# main.net
KiCad netlist of a schematic drawn in Altium Designer
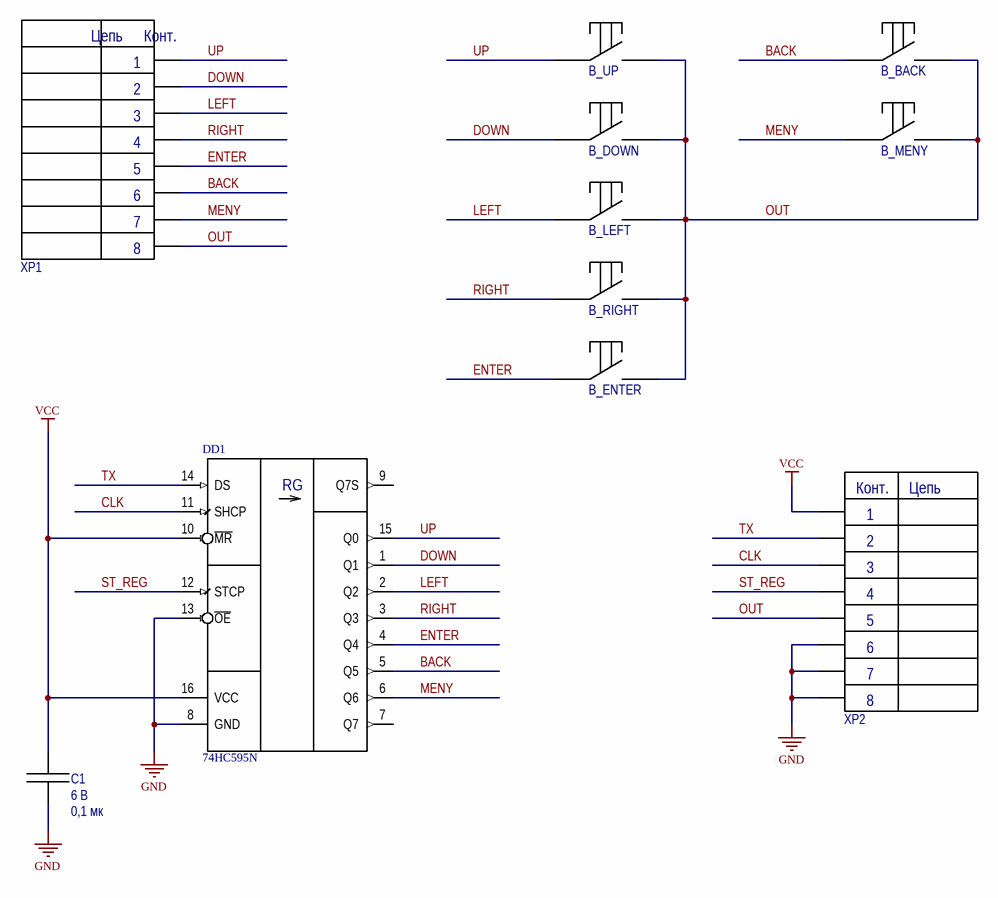
[diagram p0: main.SchDoc]

(export (version "E")
  (design (tool "Eeschema 10.0.6"))
  (components
    (comp (ref "B_BACK")
      (value "Tact_switch")
      (footprint "Tact_switch_6x6x5")
      (description "SMD pushbutton")
      (fields (field (name "MANUFACTURER") "NONAME"))
      (libsource (lib "connectors+switches") (part "Tact_switch"))
    )
    (comp (ref "B_DOWN")
      (value "Tact_switch")
      (footprint "Tact_switch_6x6x5")
      (description "SMD pushbutton")
      (fields (field (name "MANUFACTURER") "NONAME"))
      (libsource (lib "connectors+switches") (part "Tact_switch"))
    )
    (comp (ref "B_ENTER")
      (value "Tact_switch")
      (footprint "Tact_switch_6x6x5")
      (description "SMD pushbutton")
      (fields (field (name "MANUFACTURER") "NONAME"))
      (libsource (lib "connectors+switches") (part "Tact_switch"))
    )
    (comp (ref "B_LEFT")
      (value "Tact_switch")
      (footprint "Tact_switch_6x6x5")
      (description "SMD pushbutton")
      (fields (field (name "MANUFACTURER") "NONAME"))
      (libsource (lib "connectors+switches") (part "Tact_switch"))
    )
    (comp (ref "B_MENY")
      (value "Tact_switch")
      (footprint "Tact_switch_6x6x5")
      (description "SMD pushbutton")
      (fields (field (name "MANUFACTURER") "NONAME"))
      (libsource (lib "connectors+switches") (part "Tact_switch"))
    )
    (comp (ref "B_RIGHT")
      (value "Tact_switch")
      (footprint "Tact_switch_6x6x5")
      (description "SMD pushbutton")
      (fields (field (name "MANUFACTURER") "NONAME"))
      (libsource (lib "connectors+switches") (part "Tact_switch"))
    )
    (comp (ref "B_UP")
      (value "Tact_switch")
      (footprint "Tact_switch_6x6x5")
      (description "SMD pushbutton")
      (fields (field (name "MANUFACTURER") "NONAME"))
      (libsource (lib "connectors+switches") (part "Tact_switch"))
    )
    (comp (ref "C1")
      (value "0,1 мк")
      (footprint "C_1206_Manual_mount")
      (description "SMD Capacitor 1206")
      (fields
        (field (name "TOLERANCE") "/Укажите допуск в процентах/")
        (field (name "MANUFACTURER") "/Укажите компанию-производителя/")
        (field (name "RATED VOLTAGE") "6 В")
      )
      (libsource (lib "passive") (part "Capacitor 1206"))
    )
    (comp (ref "DD1") (value "74HC595N") (footprint "SO16") (libsource (lib "my_lib") (part "74HC595N")))
    (comp (ref "XP1")
      (value "PLD-8")
      (footprint "PLD-8")
      (description "PLD connector")
      (fields (field (name "MANUFACTURER") "NONAME"))
      (libsource (lib "my_lib") (part "PLD-8"))
    )
    (comp (ref "XP2")
      (value "PLD-8")
      (footprint "PLD-8")
      (description "PLD connector")
      (fields (field (name "MANUFACTURER") "NONAME"))
      (libsource (lib "my_lib") (part "PLD-8"))
    )
  )
  (nets
    (net (code "1") (name "/BACK") (class "Default")
      (node (ref "B_BACK") (pin "1") (pinfunction "1_1") (pintype "passive"))
      (node (ref "DD1") (pin "5") (pinfunction "Q5_5") (pintype "output"))
      (node (ref "XP1") (pin "6") (pinfunction "6_6") (pintype "passive"))
    )
    (net (code "2") (name "/CLK") (class "Default")
      (node (ref "DD1") (pin "11") (pinfunction "SHCP_11") (pintype "input"))
      (node (ref "XP2") (pin "3") (pinfunction "3_3") (pintype "passive"))
    )
    (net (code "3") (name "/DOWN") (class "Default")
      (node (ref "B_DOWN") (pin "1") (pinfunction "1_1") (pintype "passive"))
      (node (ref "DD1") (pin "1") (pinfunction "Q1_1") (pintype "output"))
      (node (ref "XP1") (pin "2") (pinfunction "2_2") (pintype "passive"))
    )
    (net (code "4") (name "/ENTER") (class "Default")
      (node (ref "B_ENTER") (pin "1") (pinfunction "1_1") (pintype "passive"))
      (node (ref "DD1") (pin "4") (pinfunction "Q4_4") (pintype "output"))
      (node (ref "XP1") (pin "5") (pinfunction "5_5") (pintype "passive"))
    )
    (net (code "5") (name "/LEFT") (class "Default")
      (node (ref "B_LEFT") (pin "1") (pinfunction "1_1") (pintype "passive"))
      (node (ref "DD1") (pin "2") (pinfunction "Q2_2") (pintype "output"))
      (node (ref "XP1") (pin "3") (pinfunction "3_3") (pintype "passive"))
    )
    (net (code "6") (name "/MENY") (class "Default")
      (node (ref "B_MENY") (pin "1") (pinfunction "1_1") (pintype "passive"))
      (node (ref "DD1") (pin "6") (pinfunction "Q6_6") (pintype "output"))
      (node (ref "XP1") (pin "7") (pinfunction "7_7") (pintype "passive"))
    )
    (net (code "7") (name "/OUT") (class "Default")
      (node (ref "B_BACK") (pin "2") (pinfunction "2_2") (pintype "passive"))
      (node (ref "B_DOWN") (pin "2") (pinfunction "2_2") (pintype "passive"))
      (node (ref "B_ENTER") (pin "2") (pinfunction "2_2") (pintype "passive"))
      (node (ref "B_LEFT") (pin "2") (pinfunction "2_2") (pintype "passive"))
      (node (ref "B_MENY") (pin "2") (pinfunction "2_2") (pintype "passive"))
      (node (ref "B_RIGHT") (pin "2") (pinfunction "2_2") (pintype "passive"))
      (node (ref "B_UP") (pin "2") (pinfunction "2_2") (pintype "passive"))
      (node (ref "XP1") (pin "8") (pinfunction "8_8") (pintype "passive"))
      (node (ref "XP2") (pin "5") (pinfunction "5_5") (pintype "passive"))
    )
    (net (code "8") (name "/RIGHT") (class "Default")
      (node (ref "B_RIGHT") (pin "1") (pinfunction "1_1") (pintype "passive"))
      (node (ref "DD1") (pin "3") (pinfunction "Q3_3") (pintype "output"))
      (node (ref "XP1") (pin "4") (pinfunction "4_4") (pintype "passive"))
    )
    (net (code "9") (name "/ST_REG") (class "Default")
      (node (ref "DD1") (pin "12") (pinfunction "STCP_12") (pintype "input"))
      (node (ref "XP2") (pin "4") (pinfunction "4_4") (pintype "passive"))
    )
    (net (code "10") (name "/TX") (class "Default")
      (node (ref "DD1") (pin "14") (pinfunction "DS_14") (pintype "input"))
      (node (ref "XP2") (pin "2") (pinfunction "2_2") (pintype "passive"))
    )
    (net (code "11") (name "/UP") (class "Default")
      (node (ref "B_UP") (pin "1") (pinfunction "1_1") (pintype "passive"))
      (node (ref "DD1") (pin "15") (pinfunction "Q0_15") (pintype "output"))
      (node (ref "XP1") (pin "1") (pinfunction "1_1") (pintype "passive"))
    )
    (net (code "12") (name "GND") (class "Default")
      (node (ref "C1") (pin "2") (pinfunction "2_2") (pintype "passive"))
      (node (ref "DD1") (pin "13") (pinfunction "~{OE}_13") (pintype "input"))
      (node (ref "DD1") (pin "8") (pinfunction "GND_8") (pintype "power_in"))
      (node (ref "XP2") (pin "6") (pinfunction "6_6") (pintype "passive"))
      (node (ref "XP2") (pin "7") (pinfunction "7_7") (pintype "passive"))
      (node (ref "XP2") (pin "8") (pinfunction "8_8") (pintype "passive"))
    )
    (net (code "13") (name "VCC") (class "Default")
      (node (ref "C1") (pin "1") (pinfunction "1_1") (pintype "passive"))
      (node (ref "DD1") (pin "10") (pinfunction "~{MR}_10") (pintype "input"))
      (node (ref "DD1") (pin "16") (pinfunction "VCC_16") (pintype "power_in"))
      (node (ref "XP2") (pin "1") (pinfunction "1_1") (pintype "passive"))
    )
    (net (code "14") (name "unconnected-(DD1-Q7-Pad7)") (class "Default")
      (node (ref "DD1") (pin "7") (pinfunction "Q7_7") (pintype "output"))
    )
    (net (code "15") (name "unconnected-(DD1-Q7S-Pad9)") (class "Default")
      (node (ref "DD1") (pin "9") (pinfunction "Q7S_9") (pintype "output"))
    )
  )
)
